# 06-USB_PORTS.net
KiCad netlist of a schematic drawn in Altium Designer
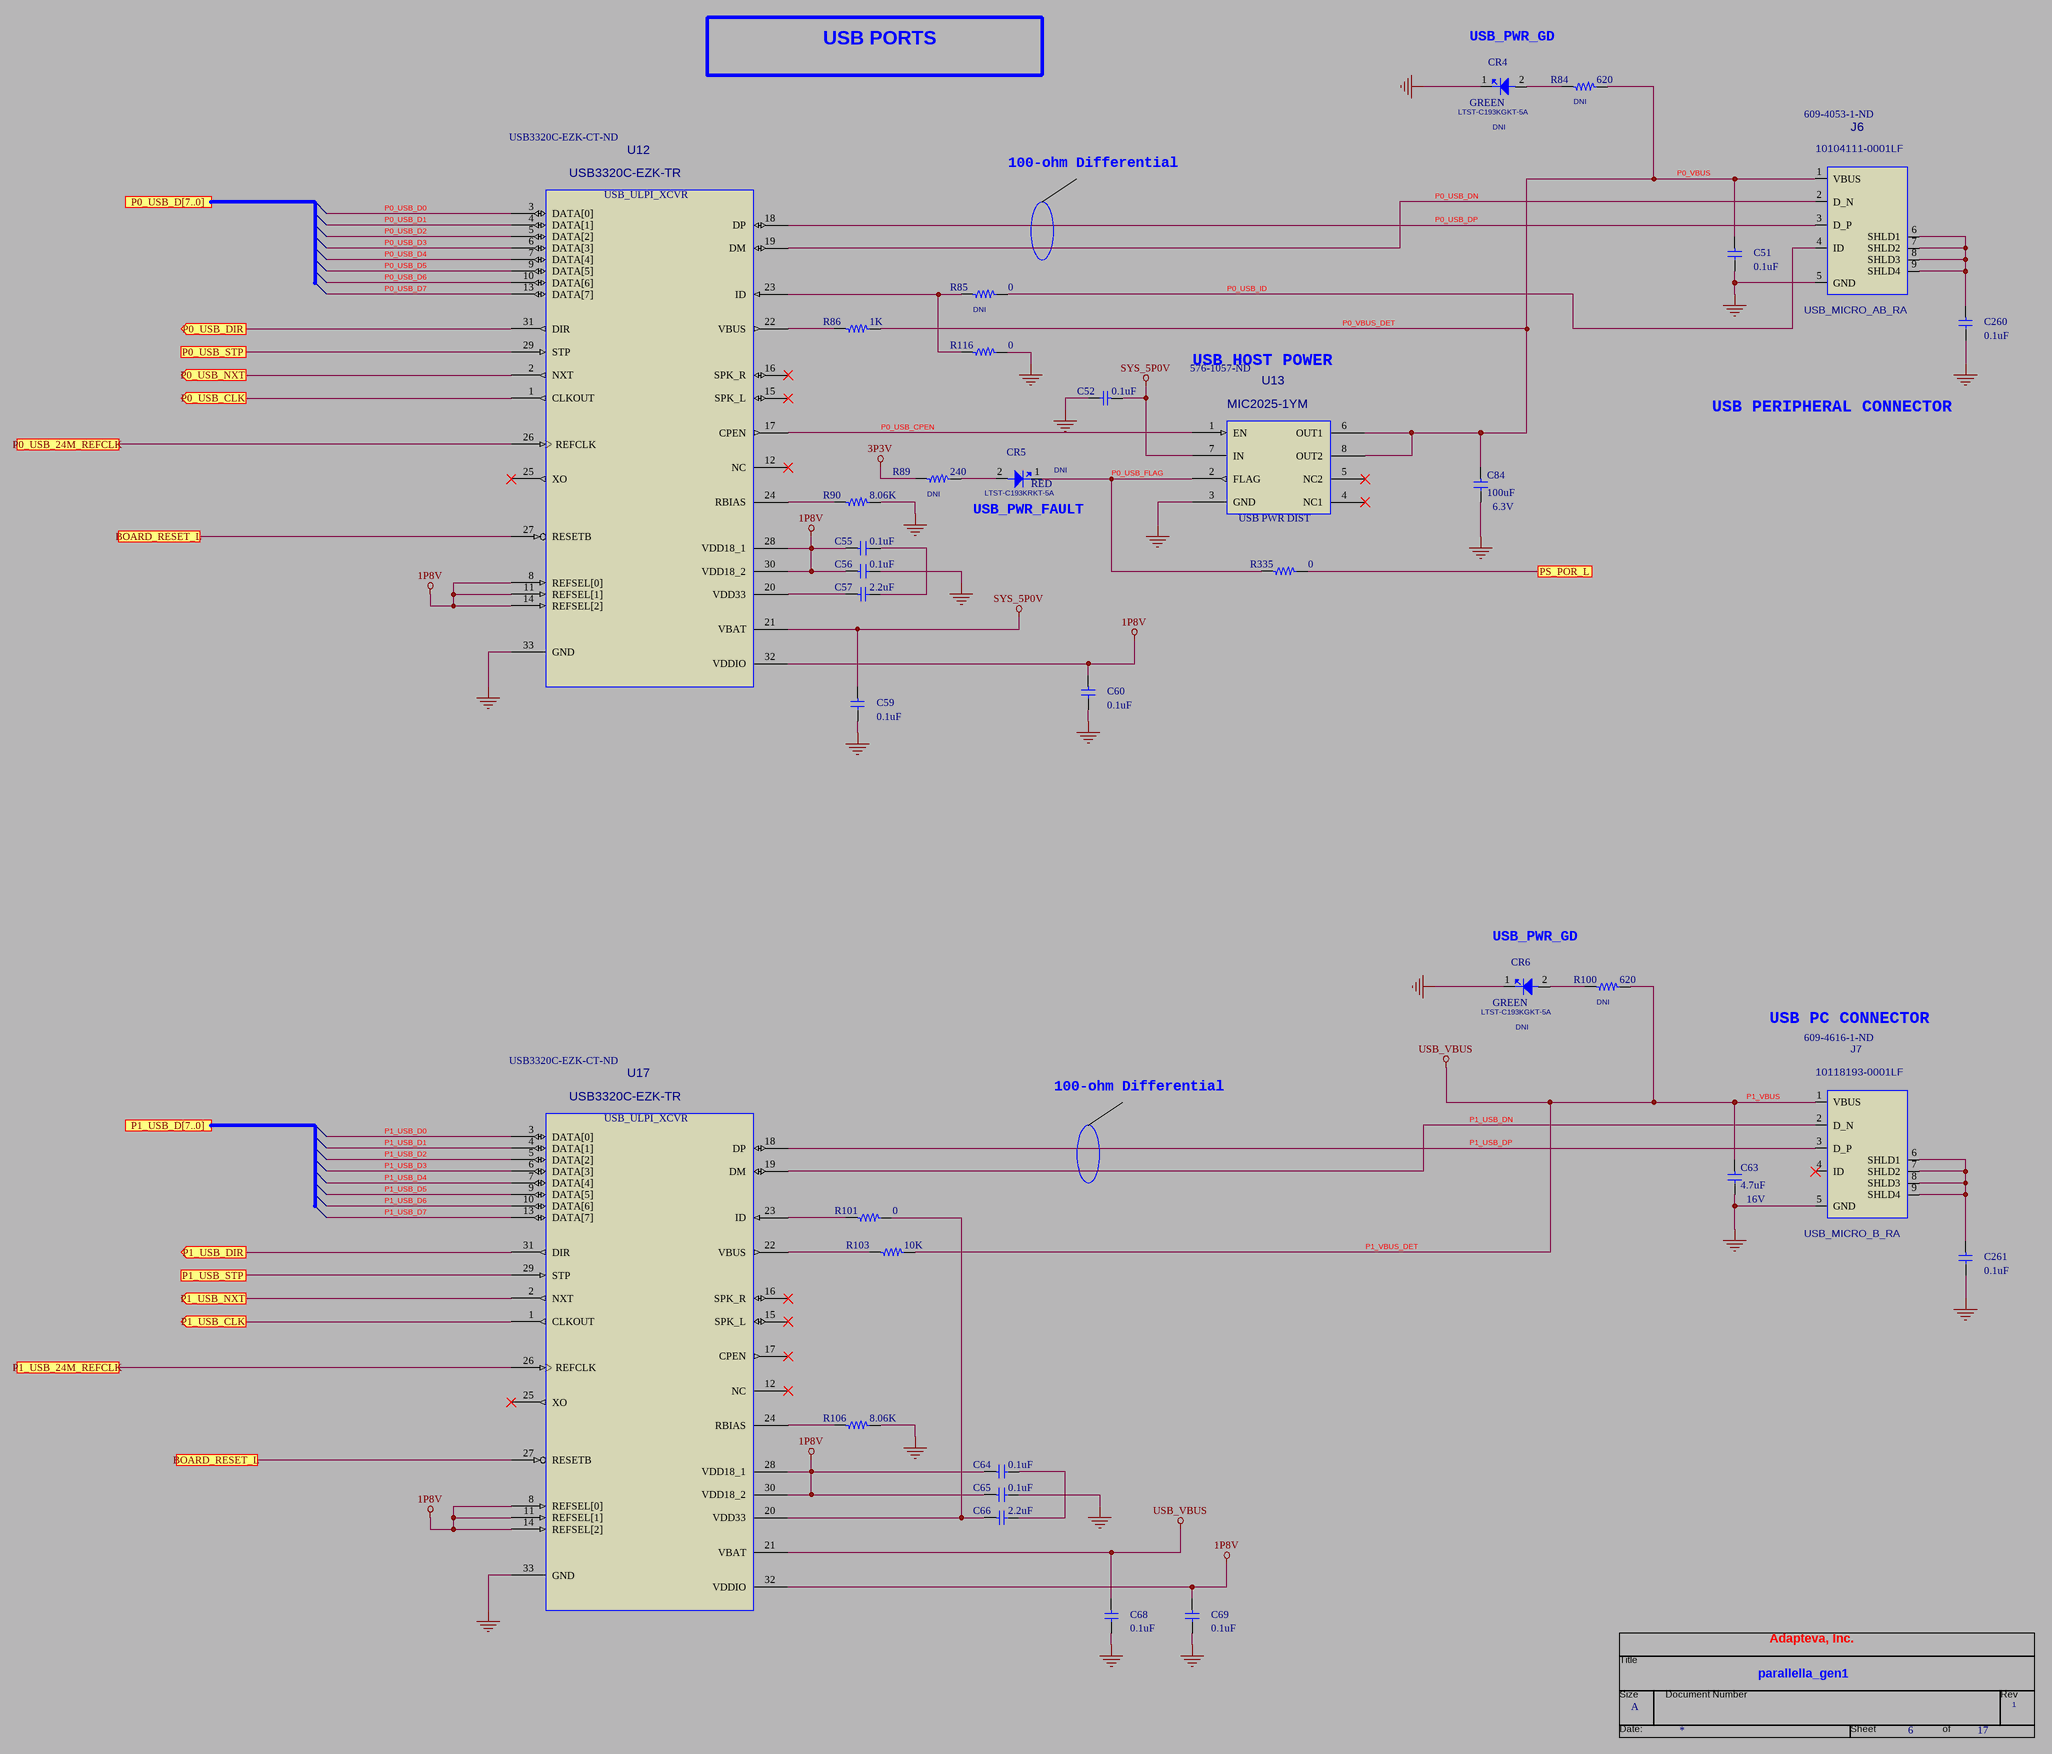
[diagram p0: 06-USB PORTS.SchDoc]

(export (version "E")
  (design (tool "Eeschema 10.0.6"))
  (components
    (comp (ref "C51")
      (value "0.1uF")
      (footprint "C0402")
      (description "CAP, 0402, 0.1UF, X5R, 35V")
      (fields (field (name "MFG PART NO") "GMK105BJ104KV-F") (field (name "MFG") "TAIYO YUDEN"))
      (libsource (lib "*") (part "CAP0402_0P1UF_X5R_35V"))
    )
    (comp (ref "C52")
      (value "0.1uF")
      (footprint "C0402")
      (description "CAP, 0402, 0.1UF, X5R, 35V")
      (fields (field (name "MFG PART NO") "GMK105BJ104KV-F") (field (name "MFG") "TAIYO YUDEN"))
      (libsource (lib "*") (part "CAP0402_0P1UF_X5R_35V"))
    )
    (comp (ref "C55")
      (value "0.1uF")
      (footprint "C0402")
      (description "CAP, 0402, 0.1UF, X5R, 35V")
      (fields (field (name "MFG PART NO") "GMK105BJ104KV-F") (field (name "MFG") "TAIYO YUDEN"))
      (libsource (lib "*") (part "CAP0402_0P1UF_X5R_35V"))
    )
    (comp (ref "C56")
      (value "0.1uF")
      (footprint "C0402")
      (description "CAP, 0402, 0.1UF, X5R, 35V")
      (fields (field (name "MFG PART NO") "GMK105BJ104KV-F") (field (name "MFG") "TAIYO YUDEN"))
      (libsource (lib "*") (part "CAP0402_0P1UF_X5R_35V"))
    )
    (comp (ref "C57")
      (value "2.2uF")
      (footprint "C0402")
      (description "CAP, 0402, 2.2UF, X5R, 6.3V")
      (fields (field (name "MFG PART NO") "C1005X5R0J225M") (field (name "MFG") "TDK"))
      (libsource (lib "*") (part "CAP0402_2P2UF_X5R"))
    )
    (comp (ref "C59")
      (value "0.1uF")
      (footprint "C0402")
      (description "CAP, 0402, 0.1UF, X5R, 35V")
      (fields (field (name "MFG PART NO") "GMK105BJ104KV-F") (field (name "MFG") "TAIYO YUDEN"))
      (libsource (lib "*") (part "CAP0402_0P1UF_X5R_35V"))
    )
    (comp (ref "C60")
      (value "0.1uF")
      (footprint "C0402")
      (description "CAP, 0402, 0.1UF, X5R, 35V")
      (fields (field (name "MFG PART NO") "GMK105BJ104KV-F") (field (name "MFG") "TAIYO YUDEN"))
      (libsource (lib "*") (part "CAP0402_0P1UF_X5R_35V"))
    )
    (comp (ref "C63")
      (value "4.7uF")
      (footprint "C0603")
      (description "CAP, 0603, 4.7UF, X5R, 16V")
      (fields
        (field (name "MFG") "TDK")
        (field (name "MFG PART NO") "C1608X5R1C475K080AC")
        (field (name "VOLTAGE") "16V")
      )
      (libsource (lib "*") (part "CAP0603_4P7UF_16V_X5R"))
    )
    (comp (ref "C64")
      (value "0.1uF")
      (footprint "C0402")
      (description "CAP, 0402, 0.1UF, X5R, 35V")
      (fields (field (name "MFG PART NO") "GMK105BJ104KV-F") (field (name "MFG") "TAIYO YUDEN"))
      (libsource (lib "*") (part "CAP0402_0P1UF_X5R_35V"))
    )
    (comp (ref "C65")
      (value "0.1uF")
      (footprint "C0402")
      (description "CAP, 0402, 0.1UF, X5R, 35V")
      (fields (field (name "MFG PART NO") "GMK105BJ104KV-F") (field (name "MFG") "TAIYO YUDEN"))
      (libsource (lib "*") (part "CAP0402_0P1UF_X5R_35V"))
    )
    (comp (ref "C66")
      (value "2.2uF")
      (footprint "C0402")
      (description "CAP, 0402, 2.2UF, X5R, 6.3V")
      (fields (field (name "MFG PART NO") "C1005X5R0J225M") (field (name "MFG") "TDK"))
      (libsource (lib "*") (part "CAP0402_2P2UF_X5R"))
    )
    (comp (ref "C68")
      (value "0.1uF")
      (footprint "C0402")
      (description "CAP, 0402, 0.1UF, X5R, 35V")
      (fields (field (name "MFG PART NO") "GMK105BJ104KV-F") (field (name "MFG") "TAIYO YUDEN"))
      (libsource (lib "*") (part "CAP0402_0P1UF_X5R_35V"))
    )
    (comp (ref "C69")
      (value "0.1uF")
      (footprint "C0402")
      (description "CAP, 0402, 0.1UF, X5R, 35V")
      (fields (field (name "MFG PART NO") "GMK105BJ104KV-F") (field (name "MFG") "TAIYO YUDEN"))
      (libsource (lib "*") (part "CAP0402_0P1UF_X5R_35V"))
    )
    (comp (ref "C84")
      (value "100uF")
      (footprint "C1210")
      (description "CAP, 1210, 100UF, X5R, 6.3V, LOW ESR")
      (fields
        (field (name "VOLTAGE") "6.3V")
        (field (name "MFG PART NO") "GRM32ER60J107ME20L")
        (field (name "MFG") "MURATA")
      )
      (libsource (lib "*") (part "CAP1210_100UF_X5R_LOESR"))
    )
    (comp (ref "C260")
      (value "0.1uF")
      (footprint "C0402")
      (description "CAP, 0402, 0.1UF, X5R, 35V")
      (fields (field (name "MFG PART NO") "GMK105BJ104KV-F") (field (name "MFG") "TAIYO YUDEN"))
      (libsource (lib "*") (part "CAP0402_0P1UF_X5R_35V"))
    )
    (comp (ref "C261")
      (value "0.1uF")
      (footprint "C0402")
      (description "CAP, 0402, 0.1UF, X5R, 35V")
      (fields (field (name "MFG PART NO") "GMK105BJ104KV-F") (field (name "MFG") "TAIYO YUDEN"))
      (libsource (lib "*") (part "CAP0402_0P1UF_X5R_35V"))
    )
    (comp (ref "CR4")
      (value "GREEN")
      (footprint "LED_0603")
      (description "LED, 0603, 5MA, SMT, GREEN")
      (fields
        (field (name "VOLTAGE") "2V")
        (field (name "MFG") "LITE-ON INC")
        (field (name "VENDOR PN") "LTST-C193KGKT-5A")
        (field (name "INSTALL") "DNI")
      )
      (libsource (lib "*") (part "LED_0603_5MA_GRN"))
    )
    (comp (ref "CR5")
      (value "RED")
      (footprint "LED_0603")
      (description "LED, 0603, 5MA, SMT, RED")
      (fields
        (field (name "VOLTAGE") "2V")
        (field (name "MFG") "LITE-ON INC")
        (field (name "VENDOR PN") "LTST-C193KRKT-5A")
        (field (name "INSTALL") "DNI")
      )
      (libsource (lib "*") (part "LED_0603_5MA_RED"))
    )
    (comp (ref "CR6")
      (value "GREEN")
      (footprint "LED_0603")
      (description "LED, 0603, 5MA, SMT, GREEN")
      (fields
        (field (name "VOLTAGE") "2V")
        (field (name "MFG") "LITE-ON INC")
        (field (name "VENDOR PN") "LTST-C193KGKT-5A")
        (field (name "INSTALL") "DNI")
      )
      (libsource (lib "*") (part "LED_0603_5MA_GRN"))
    )
    (comp (ref "J6")
      (value "USB_MICRO_AB_RA")
      (footprint "USB_MICRO5P_5X7X3P07MMH")
      (description "CONN, USB, RCPT, MICRO AB, RA, SMT")
      (fields
        (field (name "MFG PART NO") "10104111-0001LF")
        (field (name "MFG") "FCI")
        (field (name "SUPPLIER PART NUMBER 1") "609-4053-1-ND")
      )
      (libsource (lib "*") (part "USB_MICRO_AB_RA_SMT"))
    )
    (comp (ref "J7")
      (value "USB_MICRO_B_RA")
      (footprint "USB_MICROB_5P05X7P86X3P1MM_RH")
      (description "CONN, USB, RCPT, MICRO B, RA, SMT")
      (fields
        (field (name "MFG PART NO") "10118193-0001LF")
        (field (name "MFG") "FCI")
        (field (name "SUPPLIER PART NUMBER 1") "609-4616-1-ND")
      )
      (libsource (lib "*") (part "USB_MICRO_B_RA_SMT"))
    )
    (comp (ref "R84")
      (value "620")
      (footprint "R0402")
      (description "RES, 0402, 620, 1%")
      (fields
        (field (name "MFG") "VISHAY")
        (field (name "MFG PART NO") "CRCW0402620RFKED")
        (field (name "INSTALL") "DNI")
      )
      (libsource (lib "*") (part "RES0402_620"))
    )
    (comp (ref "R85")
      (value "0")
      (footprint "R0402")
      (description "RES, 0402, 0 OHM, 1%")
      (fields
        (field (name "MFG") "VISHAY")
        (field (name "MFG PART NO") "CRCW04020000Z0ED")
        (field (name "INSTALL") "DNI")
      )
      (libsource (lib "*") (part "RES0402_0"))
    )
    (comp (ref "R86")
      (value "1K")
      (footprint "R0402")
      (description "RES, 0402, 1K")
      (fields (field (name "MFG") "VISHAY") (field (name "MFG PART NO") "CRCW04021K00FKED"))
      (libsource (lib "*") (part "RES0402_1K"))
    )
    (comp (ref "R89")
      (value "240")
      (footprint "R0402")
      (description "RES, 0402, 240, 1%")
      (fields
        (field (name "MFG") "VISHAY")
        (field (name "MFG PART NO") "CRCW0402240RFKED")
        (field (name "INSTALL") "DNI")
      )
      (libsource (lib "*") (part "RES0402_240"))
    )
    (comp (ref "R90")
      (value "8.06K")
      (footprint "R0402")
      (description "RES, 0402, 8.06K")
      (fields (field (name "MFG") "VISHAY") (field (name "MFG PART NO") "CRCW04028K06FKED"))
      (libsource (lib "*") (part "RES0402_8K06"))
    )
    (comp (ref "R100")
      (value "620")
      (footprint "R0402")
      (description "RES, 0402, 620, 1%")
      (fields
        (field (name "MFG") "VISHAY")
        (field (name "MFG PART NO") "CRCW0402620RFKED")
        (field (name "INSTALL") "DNI")
      )
      (libsource (lib "*") (part "RES0402_620"))
    )
    (comp (ref "R101")
      (value "0")
      (footprint "R0402")
      (description "RES, 0402, 0 OHM, 1%")
      (fields (field (name "MFG") "VISHAY") (field (name "MFG PART NO") "CRCW04020000Z0ED"))
      (libsource (lib "*") (part "RES0402_0"))
    )
    (comp (ref "R103")
      (value "10K")
      (footprint "R0402")
      (description "RES, 0402, 10K")
      (fields (field (name "MFG") "VISHAY") (field (name "MFG PART NO") "CRCW040210K0FKED"))
      (libsource (lib "*") (part "RES0402_10K"))
    )
    (comp (ref "R106")
      (value "8.06K")
      (footprint "R0402")
      (description "RES, 0402, 8.06K")
      (fields (field (name "MFG") "VISHAY") (field (name "MFG PART NO") "CRCW04028K06FKED"))
      (libsource (lib "*") (part "RES0402_8K06"))
    )
    (comp (ref "R116")
      (value "0")
      (footprint "R0402")
      (description "RES, 0402, 0 OHM, 1%")
      (fields (field (name "MFG") "VISHAY") (field (name "MFG PART NO") "CRCW04020000Z0ED"))
      (libsource (lib "*") (part "RES0402_0"))
    )
    (comp (ref "R335")
      (value "0")
      (footprint "R0402")
      (description "RES, 0402, 0 OHM, 1%")
      (fields (field (name "MFG") "VISHAY") (field (name "MFG PART NO") "CRCW04020000Z0ED"))
      (libsource (lib "*") (part "RES0402_0"))
    )
    (comp (ref "U12")
      (value "USB_ULPI_XCVR")
      (footprint "QFN32_5SQXP9H_P5MMP_3P45PAD")
      (description "IC, USB ULPI XCVR, SINGLE SUPPLY, QFN32")
      (fields
        (field (name "VENDOR PN") "USB3320C-EZK-TR")
        (field (name "SUPPLIER PART NUMBER 1") "USB3320C-EZK-CT-ND")
      )
      (libsource (lib "*") (part "USB3320_ULPI_XCVR"))
    )
    (comp (ref "U13")
      (value "USB PWR DIST")
      (footprint "SOIC8_33P94X4P93X1P63H_P65P")
      (description "IC, USB DISTRIBUTION SW, 1 CH, SOIC8")
      (fields (field (name "VENDOR PN") "MIC2025-1YM") (field (name "SUPPLIER PART NUMBER 1") "576-1057-ND"))
      (libsource (lib "*") (part "MIC2025_1_USB_SW"))
    )
    (comp (ref "U17")
      (value "USB_ULPI_XCVR")
      (footprint "QFN32_5SQXP9H_P5MMP_3P45PAD")
      (description "IC, USB ULPI XCVR, SINGLE SUPPLY, QFN32")
      (fields
        (field (name "VENDOR PN") "USB3320C-EZK-TR")
        (field (name "SUPPLIER PART NUMBER 1") "USB3320C-EZK-CT-ND")
      )
      (libsource (lib "*") (part "USB3320_ULPI_XCVR"))
    )
  )
  (nets
    (net (code "1") (name "/BOARD_RESET_L") (class "Default")
      (node (ref "U12") (pin "27") (pinfunction "RESETB_27") (pintype "input"))
      (node (ref "U17") (pin "27") (pinfunction "RESETB_27") (pintype "input"))
    )
    (net (code "2") (name "/P0_USB_24M_REFCLK") (class "Default")
      (node (ref "U12") (pin "26") (pinfunction "REFCLK_26") (pintype "input"))
    )
    (net (code "3") (name "/P0_USB_CLK") (class "Default")
      (node (ref "U12") (pin "1") (pinfunction "CLKOUT_1") (pintype "output"))
    )
    (net (code "4") (name "/P0_USB_CPEN") (class "Default")
      (node (ref "U12") (pin "17") (pinfunction "CPEN_17") (pintype "output"))
      (node (ref "U13") (pin "1") (pinfunction "EN_1") (pintype "input"))
    )
    (net (code "5") (name "/P0_USB_D0") (class "Default")
      (node (ref "U12") (pin "3") (pinfunction "DATA[0]_3") (pintype "bidirectional"))
    )
    (net (code "6") (name "/P0_USB_D1") (class "Default")
      (node (ref "U12") (pin "4") (pinfunction "DATA[1]_4") (pintype "bidirectional"))
    )
    (net (code "7") (name "/P0_USB_D2") (class "Default")
      (node (ref "U12") (pin "5") (pinfunction "DATA[2]_5") (pintype "bidirectional"))
    )
    (net (code "8") (name "/P0_USB_D3") (class "Default")
      (node (ref "U12") (pin "6") (pinfunction "DATA[3]_6") (pintype "bidirectional"))
    )
    (net (code "9") (name "/P0_USB_D4") (class "Default")
      (node (ref "U12") (pin "7") (pinfunction "DATA[4]_7") (pintype "bidirectional"))
    )
    (net (code "10") (name "/P0_USB_D5") (class "Default")
      (node (ref "U12") (pin "9") (pinfunction "DATA[5]_9") (pintype "bidirectional"))
    )
    (net (code "11") (name "/P0_USB_D6") (class "Default")
      (node (ref "U12") (pin "10") (pinfunction "DATA[6]_10") (pintype "bidirectional"))
    )
    (net (code "12") (name "/P0_USB_D7") (class "Default")
      (node (ref "U12") (pin "13") (pinfunction "DATA[7]_13") (pintype "bidirectional"))
    )
    (net (code "13") (name "/P0_USB_DIR") (class "Default")
      (node (ref "U12") (pin "31") (pinfunction "DIR_31") (pintype "output"))
    )
    (net (code "14") (name "/P0_USB_DN") (class "Default")
      (node (ref "J6") (pin "2") (pinfunction "D_N_2") (pintype "passive"))
      (node (ref "U12") (pin "19") (pinfunction "DM_19") (pintype "bidirectional"))
    )
    (net (code "15") (name "/P0_USB_DP") (class "Default")
      (node (ref "J6") (pin "3") (pinfunction "D_P_3") (pintype "passive"))
      (node (ref "U12") (pin "18") (pinfunction "DP_18") (pintype "bidirectional"))
    )
    (net (code "17") (name "/P0_USB_FLAG") (class "Default")
      (node (ref "CR5") (pin "1") (pinfunction "C_1") (pintype "passive"))
      (node (ref "R335") (pin "1") (pinfunction "1_1") (pintype "passive"))
      (node (ref "U13") (pin "2") (pinfunction "FLAG_2") (pintype "output"))
    )
    (net (code "18") (name "/P0_USB_ID") (class "Default")
      (node (ref "J6") (pin "4") (pinfunction "ID_4") (pintype "passive"))
      (node (ref "R85") (pin "2") (pinfunction "2_2") (pintype "passive"))
    )
    (net (code "19") (name "/P0_USB_NXT") (class "Default")
      (node (ref "U12") (pin "2") (pinfunction "NXT_2") (pintype "output"))
    )
    (net (code "20") (name "/P0_USB_STP") (class "Default")
      (node (ref "U12") (pin "29") (pinfunction "STP_29") (pintype "input"))
    )
    (net (code "21") (name "/P0_VBUS") (class "Default")
      (node (ref "C51") (pin "1") (pinfunction "1_1") (pintype "passive"))
      (node (ref "C84") (pin "1") (pinfunction "1_1") (pintype "passive"))
      (node (ref "J6") (pin "1") (pinfunction "VBUS_1") (pintype "passive"))
      (node (ref "R84") (pin "2") (pinfunction "2_2") (pintype "passive"))
      (node (ref "R86") (pin "2") (pinfunction "2_2") (pintype "passive"))
      (node (ref "U13") (pin "6") (pinfunction "OUT1_6") (pintype "power_in"))
      (node (ref "U13") (pin "8") (pinfunction "OUT2_8") (pintype "power_in"))
    )
    (net (code "22") (name "/P1_USB_24M_REFCLK") (class "Default")
      (node (ref "U17") (pin "26") (pinfunction "REFCLK_26") (pintype "input"))
    )
    (net (code "23") (name "/P1_USB_CLK") (class "Default")
      (node (ref "U17") (pin "1") (pinfunction "CLKOUT_1") (pintype "output"))
    )
    (net (code "24") (name "/P1_USB_D0") (class "Default")
      (node (ref "U17") (pin "3") (pinfunction "DATA[0]_3") (pintype "bidirectional"))
    )
    (net (code "25") (name "/P1_USB_D1") (class "Default")
      (node (ref "U17") (pin "4") (pinfunction "DATA[1]_4") (pintype "bidirectional"))
    )
    (net (code "26") (name "/P1_USB_D2") (class "Default")
      (node (ref "U17") (pin "5") (pinfunction "DATA[2]_5") (pintype "bidirectional"))
    )
    (net (code "27") (name "/P1_USB_D3") (class "Default")
      (node (ref "U17") (pin "6") (pinfunction "DATA[3]_6") (pintype "bidirectional"))
    )
    (net (code "28") (name "/P1_USB_D4") (class "Default")
      (node (ref "U17") (pin "7") (pinfunction "DATA[4]_7") (pintype "bidirectional"))
    )
    (net (code "29") (name "/P1_USB_D5") (class "Default")
      (node (ref "U17") (pin "9") (pinfunction "DATA[5]_9") (pintype "bidirectional"))
    )
    (net (code "30") (name "/P1_USB_D6") (class "Default")
      (node (ref "U17") (pin "10") (pinfunction "DATA[6]_10") (pintype "bidirectional"))
    )
    (net (code "31") (name "/P1_USB_D7") (class "Default")
      (node (ref "U17") (pin "13") (pinfunction "DATA[7]_13") (pintype "bidirectional"))
    )
    (net (code "32") (name "/P1_USB_DIR") (class "Default")
      (node (ref "U17") (pin "31") (pinfunction "DIR_31") (pintype "output"))
    )
    (net (code "33") (name "/P1_USB_DN") (class "Default")
      (node (ref "J7") (pin "2") (pinfunction "D_N_2") (pintype "passive"))
      (node (ref "U17") (pin "19") (pinfunction "DM_19") (pintype "bidirectional"))
    )
    (net (code "34") (name "/P1_USB_DP") (class "Default")
      (node (ref "J7") (pin "3") (pinfunction "D_P_3") (pintype "passive"))
      (node (ref "U17") (pin "18") (pinfunction "DP_18") (pintype "bidirectional"))
    )
    (net (code "36") (name "/P1_USB_NXT") (class "Default")
      (node (ref "U17") (pin "2") (pinfunction "NXT_2") (pintype "output"))
    )
    (net (code "37") (name "/P1_USB_STP") (class "Default")
      (node (ref "U17") (pin "29") (pinfunction "STP_29") (pintype "input"))
    )
    (net (code "38") (name "/PS_POR_L") (class "Default")
      (node (ref "R335") (pin "2") (pinfunction "2_2") (pintype "passive"))
    )
    (net (code "39") (name "1P8V") (class "Default")
      (node (ref "C55") (pin "1") (pinfunction "1_1") (pintype "passive"))
      (node (ref "C56") (pin "1") (pinfunction "1_1") (pintype "passive"))
      (node (ref "C60") (pin "1") (pinfunction "1_1") (pintype "passive"))
      (node (ref "C64") (pin "1") (pinfunction "1_1") (pintype "passive"))
      (node (ref "C65") (pin "1") (pinfunction "1_1") (pintype "passive"))
      (node (ref "C69") (pin "1") (pinfunction "1_1") (pintype "passive"))
      (node (ref "U12") (pin "11") (pinfunction "REFSEL[1]_11") (pintype "input"))
      (node (ref "U12") (pin "14") (pinfunction "REFSEL[2]_14") (pintype "input"))
      (node (ref "U12") (pin "28") (pinfunction "VDD18_1_28") (pintype "power_in"))
      (node (ref "U12") (pin "30") (pinfunction "VDD18_2_30") (pintype "power_in"))
      (node (ref "U12") (pin "32") (pinfunction "VDDIO_32") (pintype "power_in"))
      (node (ref "U12") (pin "8") (pinfunction "REFSEL[0]_8") (pintype "input"))
      (node (ref "U17") (pin "11") (pinfunction "REFSEL[1]_11") (pintype "input"))
      (node (ref "U17") (pin "14") (pinfunction "REFSEL[2]_14") (pintype "input"))
      (node (ref "U17") (pin "28") (pinfunction "VDD18_1_28") (pintype "power_in"))
      (node (ref "U17") (pin "30") (pinfunction "VDD18_2_30") (pintype "power_in"))
      (node (ref "U17") (pin "32") (pinfunction "VDDIO_32") (pintype "power_in"))
      (node (ref "U17") (pin "8") (pinfunction "REFSEL[0]_8") (pintype "input"))
    )
    (net (code "40") (name "3P3V") (class "Default")
      (node (ref "R89") (pin "1") (pinfunction "1_1") (pintype "passive"))
    )
    (net (code "41") (name "GND") (class "Default")
      (node (ref "C260") (pin "2") (pinfunction "2_2") (pintype "passive"))
      (node (ref "C261") (pin "2") (pinfunction "2_2") (pintype "passive"))
      (node (ref "C51") (pin "2") (pinfunction "2_2") (pintype "passive"))
      (node (ref "C52") (pin "2") (pinfunction "2_2") (pintype "passive"))
      (node (ref "C56") (pin "2") (pinfunction "2_2") (pintype "passive"))
      (node (ref "C59") (pin "2") (pinfunction "2_2") (pintype "passive"))
      (node (ref "C60") (pin "2") (pinfunction "2_2") (pintype "passive"))
      (node (ref "C63") (pin "2") (pinfunction "2_2") (pintype "passive"))
      (node (ref "C65") (pin "2") (pinfunction "2_2") (pintype "passive"))
      (node (ref "C68") (pin "2") (pinfunction "2_2") (pintype "passive"))
      (node (ref "C69") (pin "2") (pinfunction "2_2") (pintype "passive"))
      (node (ref "C84") (pin "2") (pinfunction "2_2") (pintype "passive"))
      (node (ref "CR4") (pin "1") (pinfunction "C_1") (pintype "passive"))
      (node (ref "CR6") (pin "1") (pinfunction "C_1") (pintype "passive"))
      (node (ref "J6") (pin "5") (pinfunction "GND_5") (pintype "passive"))
      (node (ref "J7") (pin "5") (pinfunction "GND_5") (pintype "passive"))
      (node (ref "R106") (pin "2") (pinfunction "2_2") (pintype "passive"))
      (node (ref "R116") (pin "2") (pinfunction "2_2") (pintype "passive"))
      (node (ref "R90") (pin "2") (pinfunction "2_2") (pintype "passive"))
      (node (ref "U12") (pin "33") (pinfunction "GND_33") (pintype "power_in"))
      (node (ref "U13") (pin "3") (pinfunction "GND_3") (pintype "power_in"))
      (node (ref "U17") (pin "33") (pinfunction "GND_33") (pintype "power_in"))
    )
    (net (code "42") (name "Net-(C55-Pad2)") (class "Default")
      (node (ref "C55") (pin "2") (pinfunction "2_2") (pintype "passive"))
      (node (ref "C57") (pin "2") (pinfunction "2_2") (pintype "passive"))
    )
    (net (code "43") (name "Net-(C64-Pad2)") (class "Default")
      (node (ref "C64") (pin "2") (pinfunction "2_2") (pintype "passive"))
      (node (ref "C66") (pin "2") (pinfunction "2_2") (pintype "passive"))
    )
    (net (code "44") (name "Net-(CR4-A)") (class "Default")
      (node (ref "CR4") (pin "2") (pinfunction "A_2") (pintype "passive"))
      (node (ref "R84") (pin "1") (pinfunction "1_1") (pintype "passive"))
    )
    (net (code "45") (name "Net-(CR5-A)") (class "Default")
      (node (ref "CR5") (pin "2") (pinfunction "A_2") (pintype "passive"))
      (node (ref "R89") (pin "2") (pinfunction "2_2") (pintype "passive"))
    )
    (net (code "46") (name "Net-(CR6-A)") (class "Default")
      (node (ref "CR6") (pin "2") (pinfunction "A_2") (pintype "passive"))
      (node (ref "R100") (pin "1") (pinfunction "1_1") (pintype "passive"))
    )
    (net (code "47") (name "Net-(J6-SHLD1)") (class "Default")
      (node (ref "C260") (pin "1") (pinfunction "1_1") (pintype "passive"))
      (node (ref "J6") (pin "6") (pinfunction "SHLD1_6") (pintype "passive"))
      (node (ref "J6") (pin "7") (pinfunction "SHLD2_7") (pintype "passive"))
      (node (ref "J6") (pin "8") (pinfunction "SHLD3_8") (pintype "passive"))
      (node (ref "J6") (pin "9") (pinfunction "SHLD4_9") (pintype "passive"))
    )
    (net (code "48") (name "Net-(J7-SHLD1)") (class "Default")
      (node (ref "C261") (pin "1") (pinfunction "1_1") (pintype "passive"))
      (node (ref "J7") (pin "6") (pinfunction "SHLD1_6") (pintype "passive"))
      (node (ref "J7") (pin "7") (pinfunction "SHLD2_7") (pintype "passive"))
      (node (ref "J7") (pin "8") (pinfunction "SHLD3_8") (pintype "passive"))
      (node (ref "J7") (pin "9") (pinfunction "SHLD4_9") (pintype "passive"))
    )
    (net (code "49") (name "Net-(U12-ID)") (class "Default")
      (node (ref "R116") (pin "1") (pinfunction "1_1") (pintype "passive"))
      (node (ref "R85") (pin "1") (pinfunction "1_1") (pintype "passive"))
      (node (ref "U12") (pin "23") (pinfunction "ID_23") (pintype "input"))
    )
    (net (code "50") (name "Net-(U12-RBIAS)") (class "Default")
      (node (ref "R90") (pin "1") (pinfunction "1_1") (pintype "passive"))
      (node (ref "U12") (pin "24") (pinfunction "RBIAS_24") (pintype "passive"))
    )
    (net (code "51") (name "Net-(U12-VBUS)") (class "Default")
      (node (ref "R86") (pin "1") (pinfunction "1_1") (pintype "passive"))
      (node (ref "U12") (pin "22") (pinfunction "VBUS_22") (pintype "output"))
    )
    (net (code "52") (name "Net-(U12-VDD33)") (class "Default")
      (node (ref "C57") (pin "1") (pinfunction "1_1") (pintype "passive"))
      (node (ref "U12") (pin "20") (pinfunction "VDD33_20") (pintype "power_in"))
    )
    (net (code "53") (name "Net-(U17-ID)") (class "Default")
      (node (ref "R101") (pin "1") (pinfunction "1_1") (pintype "passive"))
      (node (ref "U17") (pin "23") (pinfunction "ID_23") (pintype "input"))
    )
    (net (code "54") (name "Net-(U17-RBIAS)") (class "Default")
      (node (ref "R106") (pin "1") (pinfunction "1_1") (pintype "passive"))
      (node (ref "U17") (pin "24") (pinfunction "RBIAS_24") (pintype "passive"))
    )
    (net (code "55") (name "Net-(U17-VBUS)") (class "Default")
      (node (ref "R103") (pin "1") (pinfunction "1_1") (pintype "passive"))
      (node (ref "U17") (pin "22") (pinfunction "VBUS_22") (pintype "output"))
    )
    (net (code "56") (name "Net-(U17-VDD33)") (class "Default")
      (node (ref "C66") (pin "1") (pinfunction "1_1") (pintype "passive"))
      (node (ref "R101") (pin "2") (pinfunction "2_2") (pintype "passive"))
      (node (ref "U17") (pin "20") (pinfunction "VDD33_20") (pintype "power_in"))
    )
    (net (code "57") (name "SYS_5P0V") (class "Default")
      (node (ref "C52") (pin "1") (pinfunction "1_1") (pintype "passive"))
      (node (ref "C59") (pin "1") (pinfunction "1_1") (pintype "passive"))
      (node (ref "U12") (pin "21") (pinfunction "VBAT_21") (pintype "power_in"))
      (node (ref "U13") (pin "7") (pinfunction "IN_7") (pintype "power_in"))
    )
    (net (code "58") (name "USB_VBUS") (class "Default")
      (node (ref "C63") (pin "1") (pinfunction "1_1") (pintype "passive"))
      (node (ref "C68") (pin "1") (pinfunction "1_1") (pintype "passive"))
      (node (ref "J7") (pin "1") (pinfunction "VBUS_1") (pintype "passive"))
      (node (ref "R100") (pin "2") (pinfunction "2_2") (pintype "passive"))
      (node (ref "R103") (pin "2") (pinfunction "2_2") (pintype "passive"))
      (node (ref "U17") (pin "21") (pinfunction "VBAT_21") (pintype "power_in"))
    )
    (net (code "59") (name "unconnected-(J7-ID-Pad4)") (class "Default")
      (node (ref "J7") (pin "4") (pinfunction "ID_4") (pintype "passive+no_connect"))
    )
    (net (code "60") (name "unconnected-(U12-NC-Pad12)") (class "Default")
      (node (ref "U12") (pin "12") (pinfunction "NC_12") (pintype "passive+no_connect"))
    )
    (net (code "61") (name "unconnected-(U12-SPK_L-Pad15)") (class "Default")
      (node (ref "U12") (pin "15") (pinfunction "SPK_L_15") (pintype "bidirectional+no_connect"))
    )
    (net (code "62") (name "unconnected-(U12-SPK_R-Pad16)") (class "Default")
      (node (ref "U12") (pin "16") (pinfunction "SPK_R_16") (pintype "bidirectional+no_connect"))
    )
    (net (code "63") (name "unconnected-(U12-XO-Pad25)") (class "Default")
      (node (ref "U12") (pin "25") (pinfunction "XO_25") (pintype "output+no_connect"))
    )
    (net (code "64") (name "unconnected-(U13-NC1-Pad4)") (class "Default")
      (node (ref "U13") (pin "4") (pinfunction "NC1_4") (pintype "passive+no_connect"))
    )
    (net (code "65") (name "unconnected-(U13-NC2-Pad5)") (class "Default")
      (node (ref "U13") (pin "5") (pinfunction "NC2_5") (pintype "passive+no_connect"))
    )
    (net (code "66") (name "unconnected-(U17-CPEN-Pad17)") (class "Default")
      (node (ref "U17") (pin "17") (pinfunction "CPEN_17") (pintype "output+no_connect"))
    )
    (net (code "67") (name "unconnected-(U17-NC-Pad12)") (class "Default")
      (node (ref "U17") (pin "12") (pinfunction "NC_12") (pintype "passive+no_connect"))
    )
    (net (code "68") (name "unconnected-(U17-SPK_L-Pad15)") (class "Default")
      (node (ref "U17") (pin "15") (pinfunction "SPK_L_15") (pintype "bidirectional+no_connect"))
    )
    (net (code "69") (name "unconnected-(U17-SPK_R-Pad16)") (class "Default")
      (node (ref "U17") (pin "16") (pinfunction "SPK_R_16") (pintype "bidirectional+no_connect"))
    )
    (net (code "70") (name "unconnected-(U17-XO-Pad25)") (class "Default")
      (node (ref "U17") (pin "25") (pinfunction "XO_25") (pintype "output+no_connect"))
    )
  )
)
